# schematic.net
KiCad netlist of a schematic drawn in EasyEDA
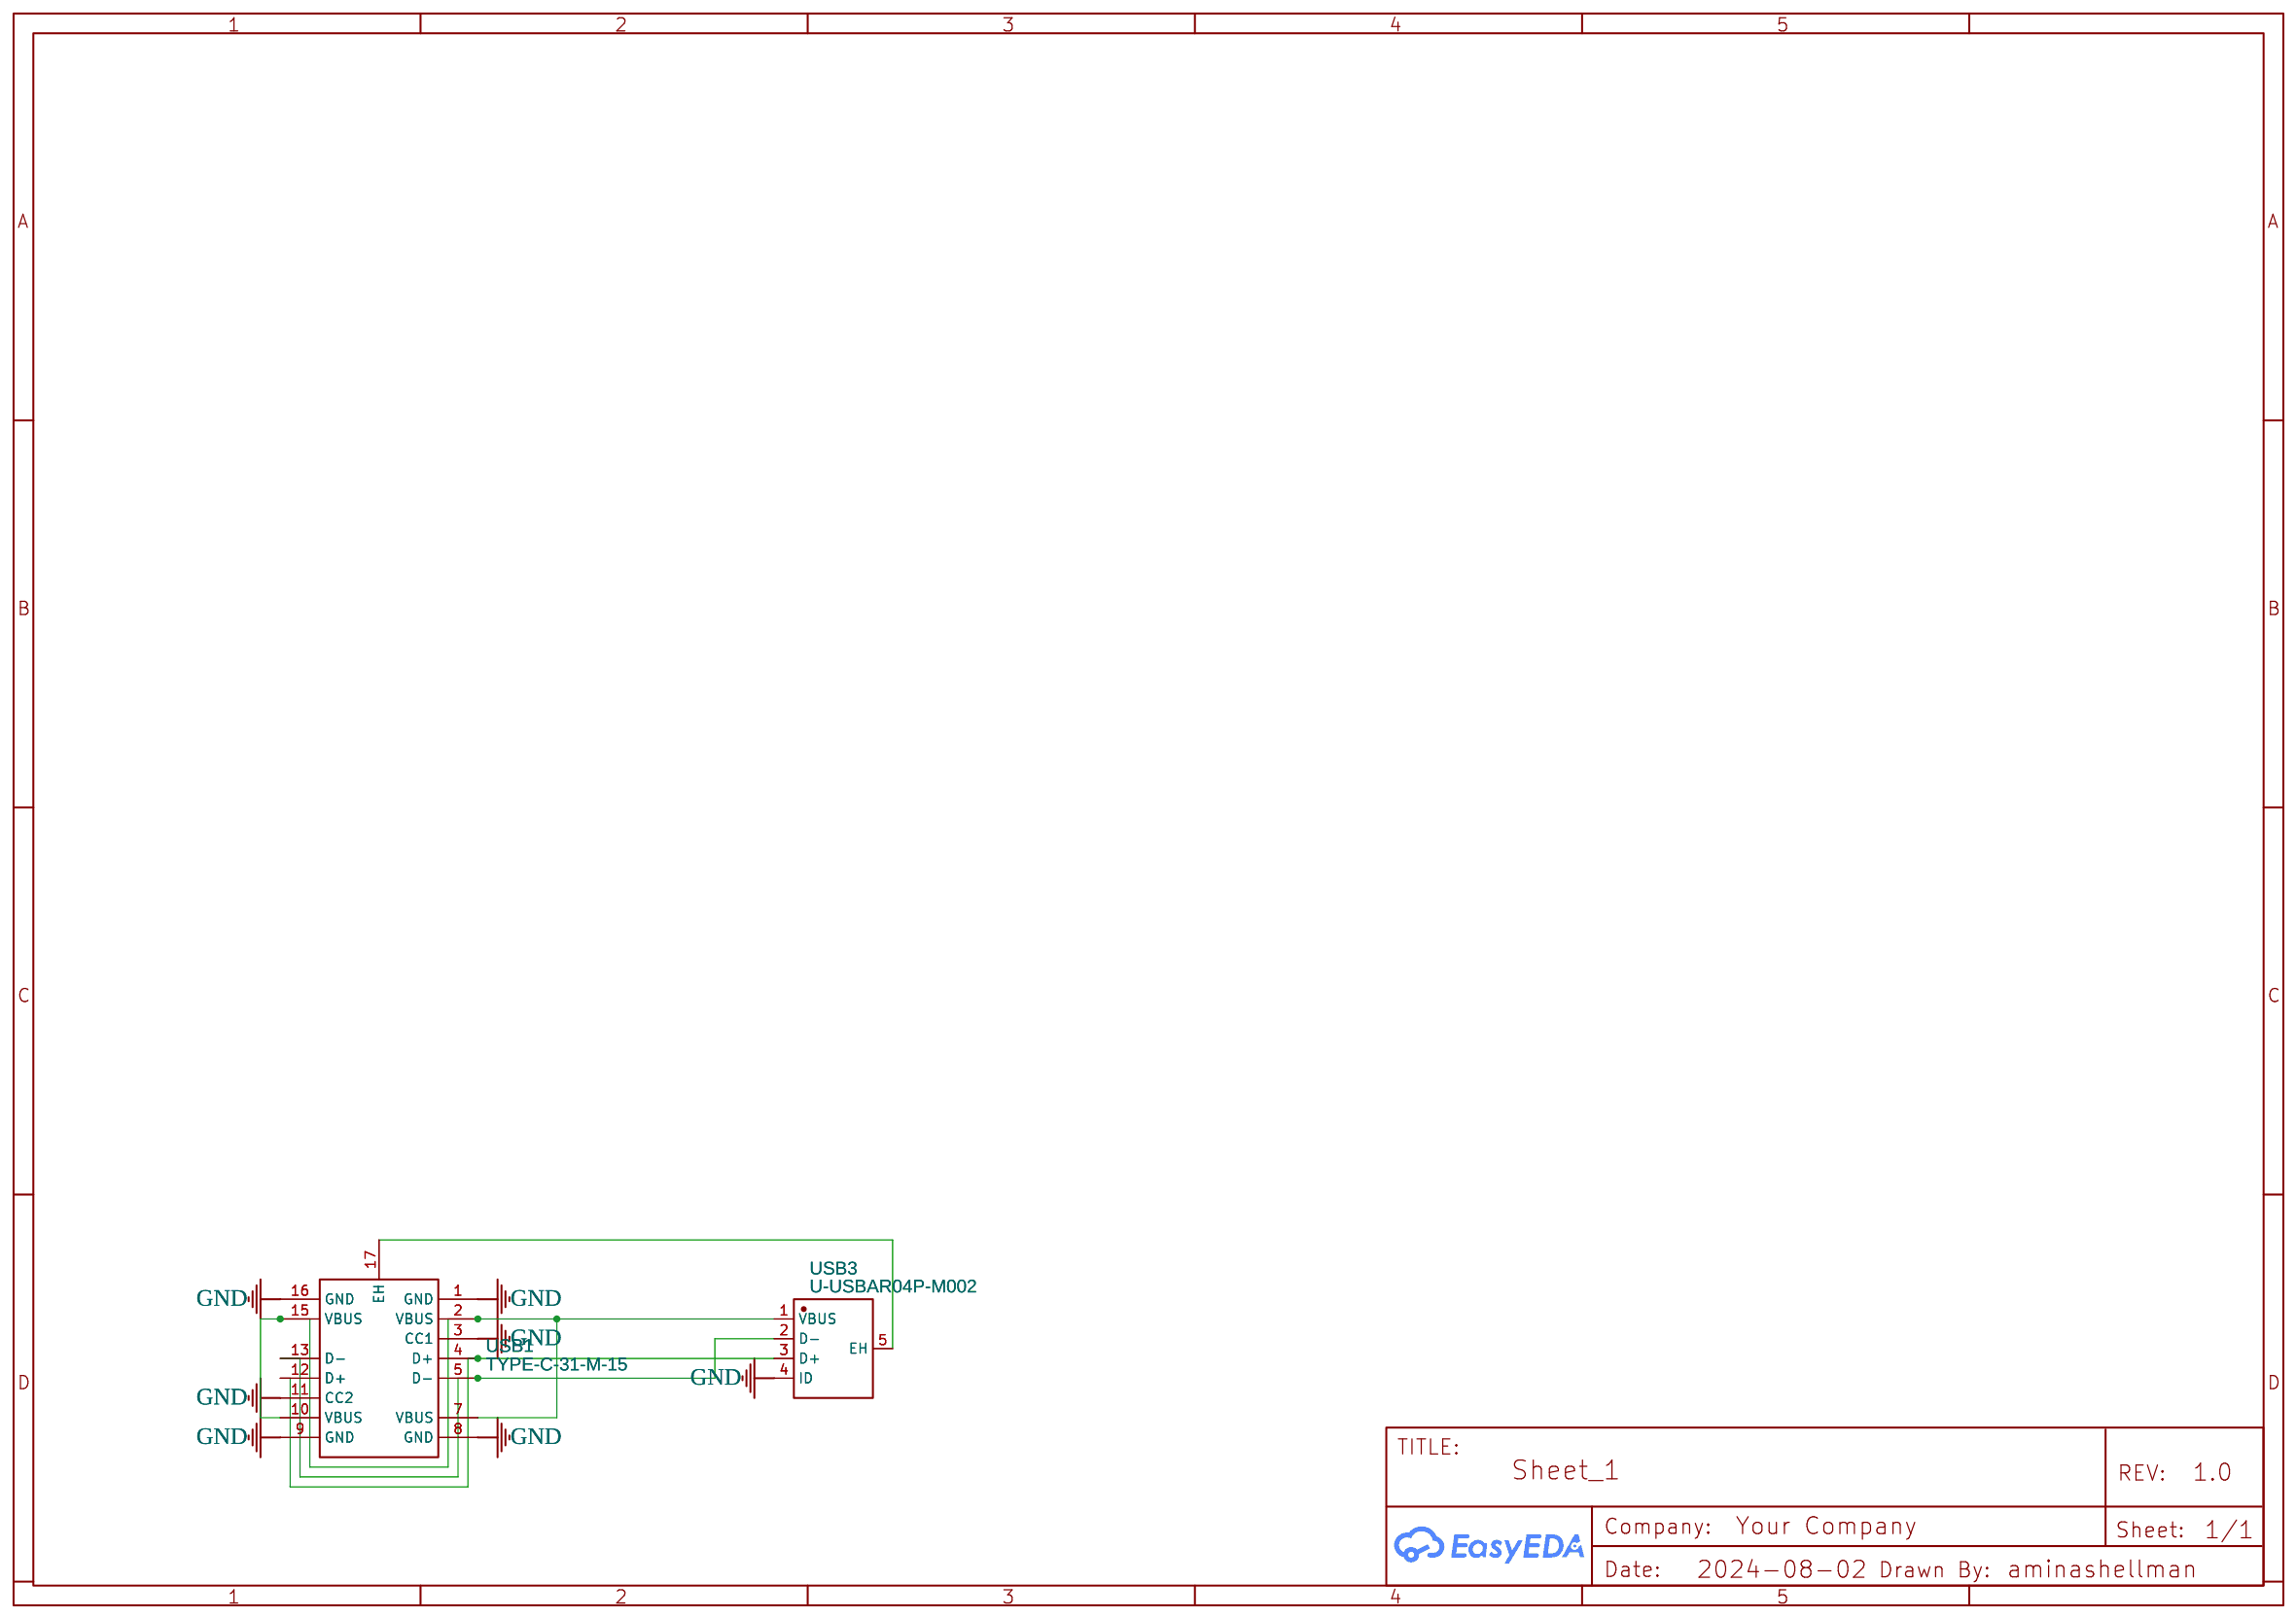
[diagram p0: schematic sheet]

(export (version "E")
  (design (tool "Eeschema 10.0.6"))
  (components
    (comp (ref "USB1")
      (value "TYPE-C-31-M-15")
      (fields (field (name "Manufacturer") "韩国韩荣"))
      (libsource (lib "") (part "TYPE-C-31-M-15"))
    )
    (comp (ref "USB3")
      (value "U-USBAR04P-M002")
      (fields (field (name "Manufacturer Part") "U-USBAR04P-M001") (field (name "Manufacturer") "Ckmtw(灿科盟)"))
      (libsource (lib "") (part "U-USBAR04P-M002"))
    )
  )
  (nets
    (net (code "1") (name "GND") (class "Default")
      (node (ref "USB1") (pin "1") (pinfunction "GND_1") (pintype "unspecified"))
      (node (ref "USB1") (pin "11") (pinfunction "CC2_11") (pintype "unspecified"))
      (node (ref "USB1") (pin "16") (pinfunction "GND_16") (pintype "unspecified"))
      (node (ref "USB1") (pin "3") (pinfunction "CC1_3") (pintype "unspecified"))
      (node (ref "USB1") (pin "8") (pinfunction "GND_8") (pintype "unspecified"))
      (node (ref "USB1") (pin "9") (pinfunction "GND_9") (pintype "unspecified"))
      (node (ref "USB3") (pin "4") (pinfunction "ID_4") (pintype "unspecified"))
    )
    (net (code "2") (name "Net-(USB1-EH)") (class "Default")
      (node (ref "USB1") (pin "17") (pinfunction "EH_17") (pintype "unspecified"))
      (node (ref "USB3") (pin "5") (pinfunction "EH_5") (pintype "unspecified"))
    )
    (net (code "3") (name "Net-(USB3-D+)") (class "Default")
      (node (ref "USB1") (pin "12") (pinfunction "D+_12") (pintype "unspecified"))
      (node (ref "USB1") (pin "4") (pinfunction "D+_4") (pintype "unspecified"))
      (node (ref "USB3") (pin "3") (pinfunction "D+_3") (pintype "unspecified"))
    )
    (net (code "4") (name "Net-(USB3-D-)") (class "Default")
      (node (ref "USB1") (pin "13") (pinfunction "D-_13") (pintype "unspecified"))
      (node (ref "USB1") (pin "5") (pinfunction "D-_5") (pintype "unspecified"))
      (node (ref "USB3") (pin "2") (pinfunction "D-_2") (pintype "unspecified"))
    )
    (net (code "5") (name "Net-(USB3-VBUS)") (class "Default")
      (node (ref "USB1") (pin "10") (pinfunction "VBUS_10") (pintype "unspecified"))
      (node (ref "USB1") (pin "15") (pinfunction "VBUS_15") (pintype "unspecified"))
      (node (ref "USB1") (pin "2") (pinfunction "VBUS_2") (pintype "unspecified"))
      (node (ref "USB1") (pin "7") (pinfunction "VBUS_7") (pintype "unspecified"))
      (node (ref "USB3") (pin "1") (pinfunction "VBUS_1") (pintype "unspecified"))
    )
  )
)
